# Dummy_load_2__4-30V_0-4_25A__v1_2.net
KiCad netlist of a schematic drawn in EAGLE
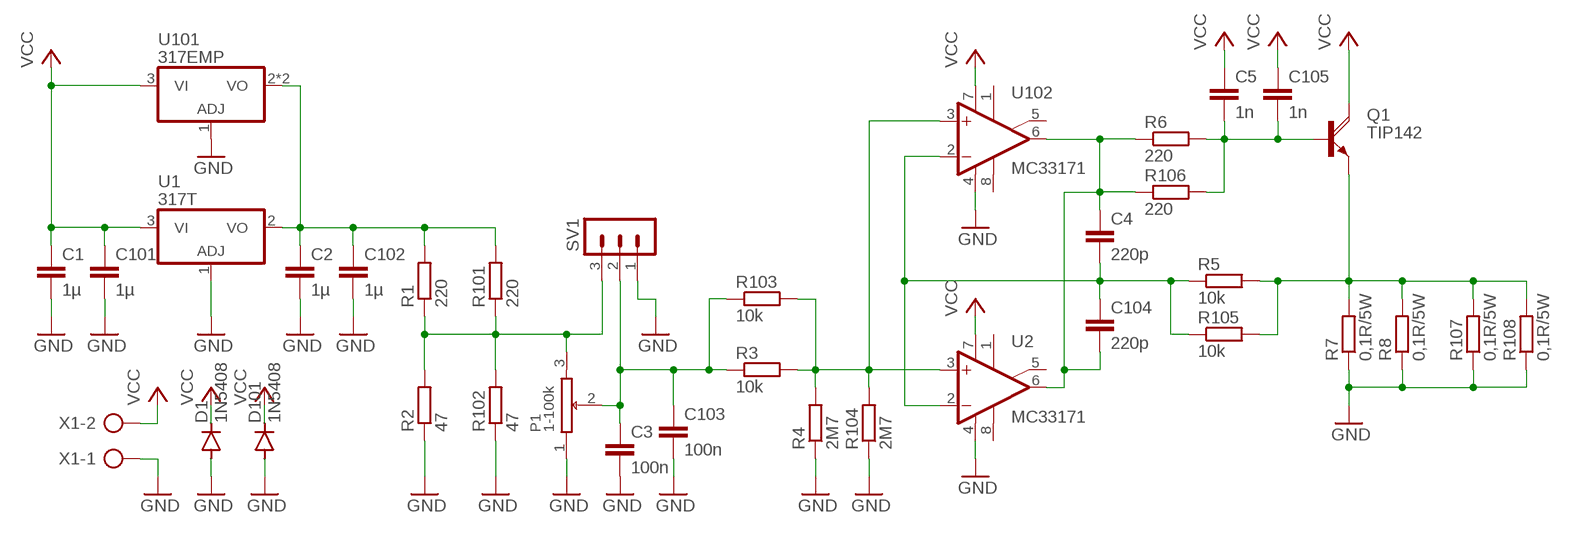
[diagram p0: schematic, sheet 1]

(export (version "E")
  (design (tool "Eeschema 10.0.6"))
  (components
    (comp (ref "C1")
      (value "1µ")
      (footprint "eagle-import:C050-024X044")
      (libsource (lib "eagle-import") (part "C-EU050-024X044"))
    )
    (comp (ref "C2")
      (value "1µ")
      (footprint "eagle-import:C050-024X044")
      (libsource (lib "eagle-import") (part "C-EU050-024X044"))
    )
    (comp (ref "C3")
      (value "100n")
      (footprint "eagle-import:C050-024X044")
      (libsource (lib "eagle-import") (part "C-EU050-024X044"))
    )
    (comp (ref "C4")
      (value "220p")
      (footprint "eagle-import:C050-024X044")
      (libsource (lib "eagle-import") (part "C-EU050-024X044"))
    )
    (comp (ref "C5")
      (value "1n")
      (footprint "eagle-import:C050-024X044")
      (libsource (lib "eagle-import") (part "C-EU050-024X044"))
    )
    (comp (ref "C101")
      (value "1µ")
      (footprint "eagle-import:C1206")
      (libsource (lib "eagle-import") (part "C-EUC1206"))
    )
    (comp (ref "C102")
      (value "1µ")
      (footprint "eagle-import:C1206")
      (libsource (lib "eagle-import") (part "C-EUC1206"))
    )
    (comp (ref "C103")
      (value "100n")
      (footprint "eagle-import:C1206")
      (libsource (lib "eagle-import") (part "C-EUC1206"))
    )
    (comp (ref "C104")
      (value "220p")
      (footprint "eagle-import:C1206")
      (libsource (lib "eagle-import") (part "C-EUC1206"))
    )
    (comp (ref "C105")
      (value "1n")
      (footprint "eagle-import:C1206")
      (libsource (lib "eagle-import") (part "C-EUC1206"))
    )
    (comp (ref "D1")
      (value "1N5408")
      (footprint "eagle-import:C1702-06")
      (libsource (lib "eagle-import") (part "DIODE-C1702-06"))
    )
    (comp (ref "D101")
      (value "1N5408")
      (footprint "eagle-import:DO214AA")
      (libsource (lib "eagle-import") (part "DIODE-DO214AA"))
    )
    (comp (ref "P1")
      (value "1-100k")
      (footprint "eagle-import:POT1_POTH_1")
      (libsource (lib "eagle-import") (part "POT1_POTH_1"))
    )
    (comp (ref "Q1")
      (value "TIP142")
      (footprint "eagle-import:SOT93V")
      (libsource (lib "eagle-import") (part "TIP142VERTICAL"))
    )
    (comp (ref "R1")
      (value "220")
      (footprint "eagle-import:0207_10")
      (libsource (lib "eagle-import") (part "R-EU_0207/10"))
    )
    (comp (ref "R2")
      (value "47")
      (footprint "eagle-import:0207_10")
      (libsource (lib "eagle-import") (part "R-EU_0207/10"))
    )
    (comp (ref "R3")
      (value "10k")
      (footprint "eagle-import:0207_10")
      (libsource (lib "eagle-import") (part "R-EU_0207/10"))
    )
    (comp (ref "R4")
      (value "2M7")
      (footprint "eagle-import:0207_10")
      (libsource (lib "eagle-import") (part "R-EU_0207/10"))
    )
    (comp (ref "R5")
      (value "10k")
      (footprint "eagle-import:0207_10")
      (libsource (lib "eagle-import") (part "R-EU_0207/10"))
    )
    (comp (ref "R6")
      (value "220")
      (footprint "eagle-import:0207_10")
      (libsource (lib "eagle-import") (part "R-EU_0207/10"))
    )
    (comp (ref "R7")
      (value "0,1R/5W")
      (footprint "eagle-import:VTA53")
      (libsource (lib "eagle-import") (part "R-EU_VTA53"))
    )
    (comp (ref "R8")
      (value "0,1R/5W")
      (footprint "eagle-import:VTA53")
      (libsource (lib "eagle-import") (part "R-EU_VTA53"))
    )
    (comp (ref "R101")
      (value "220")
      (footprint "eagle-import:R1206")
      (libsource (lib "eagle-import") (part "R-EU_R1206"))
    )
    (comp (ref "R102")
      (value "47")
      (footprint "eagle-import:R1206")
      (libsource (lib "eagle-import") (part "R-EU_R1206"))
    )
    (comp (ref "R103")
      (value "10k")
      (footprint "eagle-import:R1206")
      (libsource (lib "eagle-import") (part "R-EU_R1206"))
    )
    (comp (ref "R104")
      (value "2M7")
      (footprint "eagle-import:R1206")
      (libsource (lib "eagle-import") (part "R-EU_R1206"))
    )
    (comp (ref "R105")
      (value "10k")
      (footprint "eagle-import:R1206")
      (libsource (lib "eagle-import") (part "R-EU_R1206"))
    )
    (comp (ref "R106")
      (value "220")
      (footprint "eagle-import:R1206")
      (libsource (lib "eagle-import") (part "R-EU_R1206"))
    )
    (comp (ref "R107")
      (value "0,1R/5W")
      (footprint "eagle-import:P0817V")
      (libsource (lib "eagle-import") (part "R-EU_0817/7V"))
    )
    (comp (ref "R108")
      (value "0,1R/5W")
      (footprint "eagle-import:P0817V")
      (libsource (lib "eagle-import") (part "R-EU_0817/7V"))
    )
    (comp (ref "SV1")
      (value "MA03-1")
      (footprint "eagle-import:MA03-1")
      (libsource (lib "eagle-import") (part "MA03-1"))
    )
    (comp (ref "U1")
      (value "317T")
      (footprint "eagle-import:TO220H")
      (libsource (lib "eagle-import") (part "317T"))
    )
    (comp (ref "U2")
      (value "MC33171")
      (footprint "eagle-import:DIL08")
      (libsource (lib "eagle-import") (part "741PLM"))
    )
    (comp (ref "U101")
      (value "317EMP")
      (footprint "eagle-import:SOT223")
      (libsource (lib "eagle-import") (part "317EMP"))
    )
    (comp (ref "U102")
      (value "MC33171")
      (footprint "eagle-import:SO08")
      (libsource (lib "eagle-import") (part "741DLM"))
    )
    (comp (ref "X1")
      (value "AK500/2")
      (footprint "eagle-import:AK500_2")
      (libsource (lib "eagle-import") (part "AK500/2"))
    )
  )
  (nets
    (net (code "1") (name "GND") (class "Default")
      (node (ref "C1") (pin "2") (pinfunction "2_2") (pintype "passive"))
      (node (ref "C101") (pin "2") (pinfunction "2_2") (pintype "passive"))
      (node (ref "C102") (pin "2") (pinfunction "2_2") (pintype "passive"))
      (node (ref "C103") (pin "2") (pinfunction "2_2") (pintype "passive"))
      (node (ref "C2") (pin "2") (pinfunction "2_2") (pintype "passive"))
      (node (ref "C3") (pin "2") (pinfunction "2_2") (pintype "passive"))
      (node (ref "D1") (pin "A") (pinfunction "A_A") (pintype "passive"))
      (node (ref "D101") (pin "A") (pinfunction "A_A") (pintype "passive"))
      (node (ref "P1") (pin "1") (pinfunction "1_1") (pintype "passive"))
      (node (ref "R102") (pin "1") (pinfunction "1_1") (pintype "passive"))
      (node (ref "R104") (pin "1") (pinfunction "1_1") (pintype "passive"))
      (node (ref "R107") (pin "1") (pinfunction "1_1") (pintype "passive"))
      (node (ref "R108") (pin "1") (pinfunction "1_1") (pintype "passive"))
      (node (ref "R2") (pin "1") (pinfunction "1_1") (pintype "passive"))
      (node (ref "R4") (pin "1") (pinfunction "1_1") (pintype "passive"))
      (node (ref "R7") (pin "1") (pinfunction "1_1") (pintype "passive"))
      (node (ref "R8") (pin "1") (pinfunction "1_1") (pintype "passive"))
      (node (ref "SV1") (pin "1") (pinfunction "1_1") (pintype "passive"))
      (node (ref "U1") (pin "1") (pinfunction "ADJ_1") (pintype "input"))
      (node (ref "U101") (pin "1") (pinfunction "ADJ_1") (pintype "input"))
      (node (ref "U102") (pin "4") (pinfunction "V-_4") (pintype "power_in"))
      (node (ref "U2") (pin "4") (pinfunction "V-_4") (pintype "power_in"))
      (node (ref "X1") (pin "1") (pinfunction "KL_1") (pintype "passive"))
    )
    (net (code "2") (name "Net-(C103-Pad1)") (class "Default")
      (node (ref "C103") (pin "1") (pinfunction "1_1") (pintype "passive"))
      (node (ref "C3") (pin "1") (pinfunction "1_1") (pintype "passive"))
      (node (ref "P1") (pin "2") (pinfunction "2_2") (pintype "passive"))
      (node (ref "R103") (pin "1") (pinfunction "1_1") (pintype "passive"))
      (node (ref "R3") (pin "1") (pinfunction "1_1") (pintype "passive"))
      (node (ref "SV1") (pin "2") (pinfunction "2_2") (pintype "passive"))
    )
    (net (code "3") (name "Net-(C105-Pad2)") (class "Default")
      (node (ref "C105") (pin "2") (pinfunction "2_2") (pintype "passive"))
      (node (ref "C5") (pin "2") (pinfunction "2_2") (pintype "passive"))
      (node (ref "Q1") (pin "B") (pinfunction "B_B") (pintype "passive"))
      (node (ref "R106") (pin "2") (pinfunction "2_2") (pintype "passive"))
      (node (ref "R6") (pin "2") (pinfunction "2_2") (pintype "passive"))
    )
    (net (code "4") (name "Net-(P1-Pad3)") (class "Default")
      (node (ref "P1") (pin "3") (pinfunction "3_3") (pintype "passive"))
      (node (ref "R1") (pin "1") (pinfunction "1_1") (pintype "passive"))
      (node (ref "R101") (pin "1") (pinfunction "1_1") (pintype "passive"))
      (node (ref "R102") (pin "2") (pinfunction "2_2") (pintype "passive"))
      (node (ref "R2") (pin "2") (pinfunction "2_2") (pintype "passive"))
      (node (ref "SV1") (pin "3") (pinfunction "3_3") (pintype "passive"))
    )
    (net (code "5") (name "Net-(Q1-PadE)") (class "Default")
      (node (ref "Q1") (pin "E") (pinfunction "E_E") (pintype "passive"))
      (node (ref "R105") (pin "2") (pinfunction "2_2") (pintype "passive"))
      (node (ref "R107") (pin "2") (pinfunction "2_2") (pintype "passive"))
      (node (ref "R108") (pin "2") (pinfunction "2_2") (pintype "passive"))
      (node (ref "R5") (pin "2") (pinfunction "2_2") (pintype "passive"))
      (node (ref "R7") (pin "2") (pinfunction "2_2") (pintype "passive"))
      (node (ref "R8") (pin "2") (pinfunction "2_2") (pintype "passive"))
    )
    (net (code "6") (name "Net-(U1-VO)") (class "Default")
      (node (ref "C102") (pin "1") (pinfunction "1_1") (pintype "passive"))
      (node (ref "C2") (pin "1") (pinfunction "1_1") (pintype "passive"))
      (node (ref "R1") (pin "2") (pinfunction "2_2") (pintype "passive"))
      (node (ref "R101") (pin "2") (pinfunction "2_2") (pintype "passive"))
      (node (ref "U1") (pin "2") (pinfunction "VO_2") (pintype "passive"))
      (node (ref "U101") (pin "2") (pinfunction "VO_2") (pintype "passive"))
      (node (ref "U101") (pin "4") (pinfunction "VO_4") (pintype "passive"))
    )
    (net (code "7") (name "Net-(U102-+IN)") (class "Default")
      (node (ref "R103") (pin "2") (pinfunction "2_2") (pintype "passive"))
      (node (ref "R104") (pin "2") (pinfunction "2_2") (pintype "passive"))
      (node (ref "R3") (pin "2") (pinfunction "2_2") (pintype "passive"))
      (node (ref "R4") (pin "2") (pinfunction "2_2") (pintype "passive"))
      (node (ref "U102") (pin "3") (pinfunction "+IN_3") (pintype "input"))
      (node (ref "U2") (pin "3") (pinfunction "+IN_3") (pintype "input"))
    )
    (net (code "8") (name "Net-(U102--IN)") (class "Default")
      (node (ref "C104") (pin "1") (pinfunction "1_1") (pintype "passive"))
      (node (ref "C4") (pin "2") (pinfunction "2_2") (pintype "passive"))
      (node (ref "R105") (pin "1") (pinfunction "1_1") (pintype "passive"))
      (node (ref "R5") (pin "1") (pinfunction "1_1") (pintype "passive"))
      (node (ref "U102") (pin "2") (pinfunction "-IN_2") (pintype "input"))
      (node (ref "U2") (pin "2") (pinfunction "-IN_2") (pintype "input"))
    )
    (net (code "9") (name "Net-(U102-OUT)") (class "Default")
      (node (ref "C104") (pin "2") (pinfunction "2_2") (pintype "passive"))
      (node (ref "C4") (pin "1") (pinfunction "1_1") (pintype "passive"))
      (node (ref "R106") (pin "1") (pinfunction "1_1") (pintype "passive"))
      (node (ref "R6") (pin "1") (pinfunction "1_1") (pintype "passive"))
      (node (ref "U102") (pin "6") (pinfunction "OUT_6") (pintype "output"))
      (node (ref "U2") (pin "6") (pinfunction "OUT_6") (pintype "output"))
    )
    (net (code "10") (name "VCC") (class "Default")
      (node (ref "C1") (pin "1") (pinfunction "1_1") (pintype "passive"))
      (node (ref "C101") (pin "1") (pinfunction "1_1") (pintype "passive"))
      (node (ref "C105") (pin "1") (pinfunction "1_1") (pintype "passive"))
      (node (ref "C5") (pin "1") (pinfunction "1_1") (pintype "passive"))
      (node (ref "D1") (pin "C") (pinfunction "C_C") (pintype "passive"))
      (node (ref "D101") (pin "C") (pinfunction "C_C") (pintype "passive"))
      (node (ref "Q1") (pin "C") (pinfunction "C_C") (pintype "passive"))
      (node (ref "U1") (pin "3") (pinfunction "VI_3") (pintype "input"))
      (node (ref "U101") (pin "3") (pinfunction "VI_3") (pintype "input"))
      (node (ref "U102") (pin "7") (pinfunction "V+_7") (pintype "power_in"))
      (node (ref "U2") (pin "7") (pinfunction "V+_7") (pintype "power_in"))
      (node (ref "X1") (pin "2") (pinfunction "KL_2") (pintype "passive"))
    )
    (net (code "11") (name "unconnected-(U2-ON1-Pad1)") (class "Default")
      (node (ref "U2") (pin "1") (pinfunction "ON1_1") (pintype "passive"))
    )
    (net (code "12") (name "unconnected-(U2-ON2-Pad5)") (class "Default")
      (node (ref "U2") (pin "5") (pinfunction "ON2_5") (pintype "passive"))
    )
    (net (code "13") (name "unconnected-(U2-OPT-Pad8)") (class "Default")
      (node (ref "U2") (pin "8") (pinfunction "OPT_8") (pintype "passive"))
    )
    (net (code "14") (name "unconnected-(U102-ON1-Pad1)") (class "Default")
      (node (ref "U102") (pin "1") (pinfunction "ON1_1") (pintype "passive"))
    )
    (net (code "15") (name "unconnected-(U102-ON2-Pad5)") (class "Default")
      (node (ref "U102") (pin "5") (pinfunction "ON2_5") (pintype "passive"))
    )
    (net (code "16") (name "unconnected-(U102-OPT-Pad8)") (class "Default")
      (node (ref "U102") (pin "8") (pinfunction "OPT_8") (pintype "passive"))
    )
  )
)
